# Shematic.net
KiCad netlist of a schematic drawn in Altium Designer
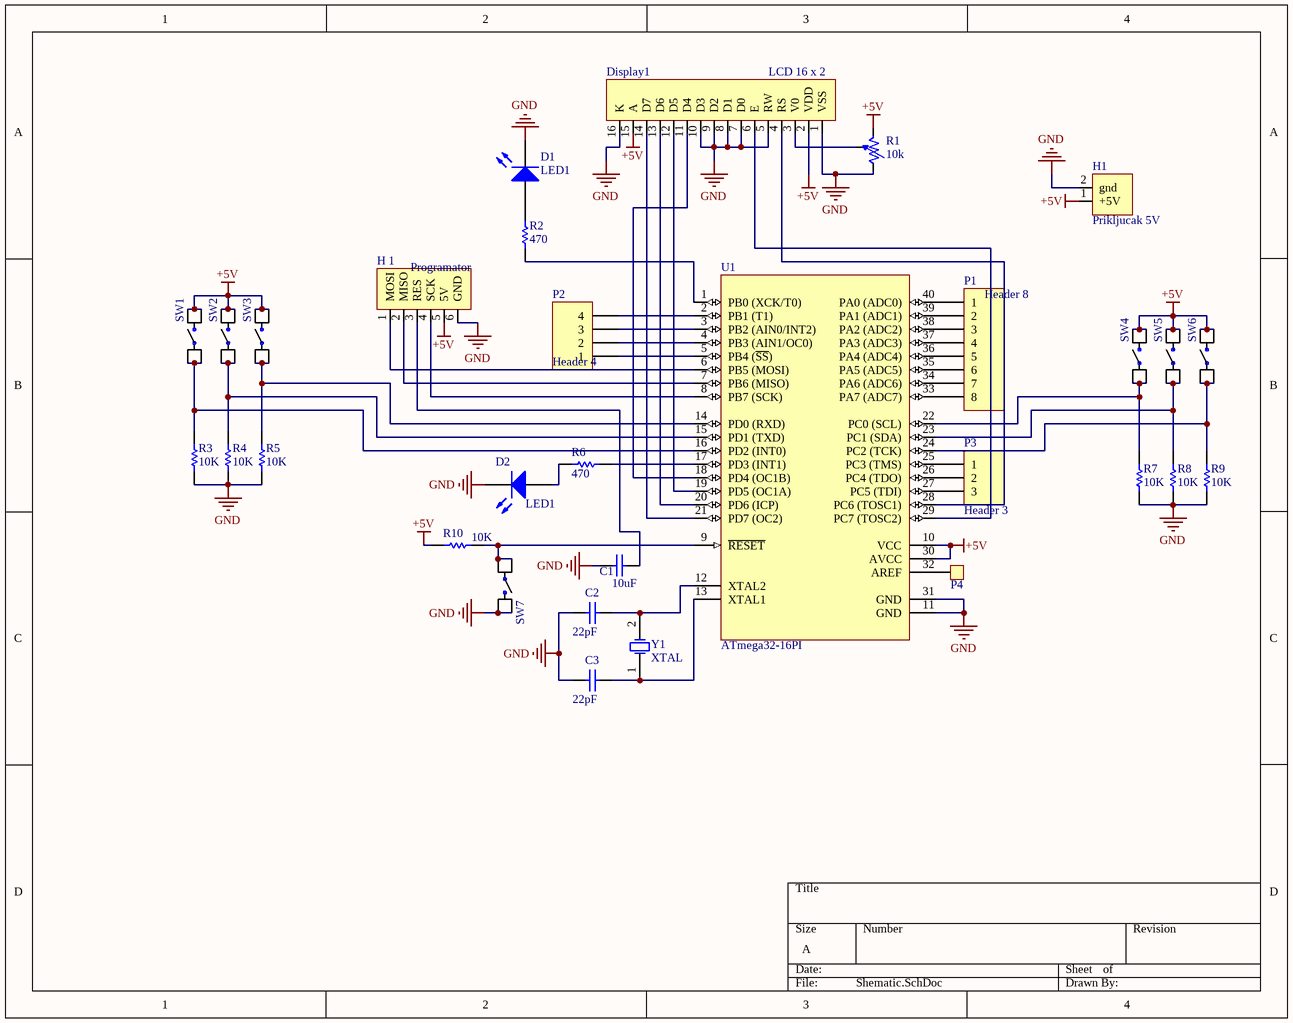
[diagram p0: Shematic.SchDoc]

(export (version "E")
  (design (tool "Eeschema 10.0.6"))
  (components
    (comp (ref "C1")
      (value "10uF")
      (footprint "RAD-0.3")
      (description "Capacitor")
      (fields (field (name "Comment") "Cap") (field (name "PUBLISHER") "Altium Limited"))
      (libsource (lib "Miscellaneous Devices") (part "Cap"))
    )
    (comp (ref "C2")
      (value "22pF")
      (footprint "RAD-0.3")
      (description "Capacitor")
      (fields (field (name "Comment") "Cap") (field (name "PUBLISHER") "Altium Limited"))
      (libsource (lib "Miscellaneous Devices") (part "Cap"))
    )
    (comp (ref "C3")
      (value "22pF")
      (footprint "RAD-0.3")
      (description "Capacitor")
      (fields (field (name "Comment") "Cap") (field (name "PUBLISHER") "Altium Limited"))
      (libsource (lib "Miscellaneous Devices") (part "Cap"))
    )
    (comp (ref "D1")
      (value "LED1")
      (footprint "LED-1")
      (description "Typical RED GaAs LED")
      (fields (field (name "PUBLISHER") "Altium Limited"))
      (libsource (lib "Miscellaneous Devices") (part "LED1"))
    )
    (comp (ref "D2")
      (value "LED1")
      (footprint "LED-1")
      (description "Typical RED GaAs LED")
      (fields (field (name "PUBLISHER") "Altium Limited"))
      (libsource (lib "Miscellaneous Devices") (part "LED1"))
    )
    (comp (ref "Display1")
      (value "LCD 16 x 2")
      (footprint "LCD16x2")
      (libsource (lib "LIB-shematic") (part "LCD 16 X 2"))
    )
    (comp (ref "H 1")
      (value "Programator")
      (footprint "USBASP")
      (libsource (lib "LIB-shematic") (part "USBASP"))
    )
    (comp (ref "H1")
      (value "Prikljucak 5V")
      (footprint "H 5V")
      (libsource (lib "LIB-shematic") (part "Header 5V"))
    )
    (comp (ref "P1")
      (value "Header 8")
      (footprint "HDR1X8")
      (description "Header, 8-Pin")
      (fields (field (name "PUBLISHER") "Altium Limited"))
      (libsource (lib "Miscellaneous Connectors") (part "Header 8"))
    )
    (comp (ref "P2")
      (value "Header 4")
      (footprint "HDR1X4")
      (description "Header, 4-Pin")
      (fields (field (name "PUBLISHER") "Altium Limited"))
      (libsource (lib "Miscellaneous Connectors") (part "Header 4"))
    )
    (comp (ref "P3")
      (value "Header 3")
      (footprint "HDR1X3")
      (description "Header, 3-Pin")
      (fields (field (name "PUBLISHER") "Altium Limited"))
      (libsource (lib "Miscellaneous Connectors") (part "Header 3"))
    )
    (comp (ref "P4")
      (value "Header 1")
      (footprint "Header 1")
      (libsource (lib "LIB-shematic") (part "Header 1"))
    )
    (comp (ref "R1") (value "10k") (footprint "ADJ_RES") (libsource (lib "LIB-shematic") (part "ADJ_RES")))
    (comp (ref "R2")
      (value "470")
      (footprint "AXIAL-0.3")
      (description "Resistor")
      (fields (field (name "Comment") "Res1") (field (name "PUBLISHER") "Altium Limited"))
      (libsource (lib "Miscellaneous Devices") (part "Res1"))
    )
    (comp (ref "R3")
      (value "10K")
      (footprint "AXIAL-0.3")
      (description "Resistor")
      (fields (field (name "Comment") "Res1") (field (name "PUBLISHER") "Altium Limited"))
      (libsource (lib "Miscellaneous Devices") (part "Res1"))
    )
    (comp (ref "R4")
      (value "10K")
      (footprint "AXIAL-0.3")
      (description "Resistor")
      (fields (field (name "Comment") "Res1") (field (name "PUBLISHER") "Altium Limited"))
      (libsource (lib "Miscellaneous Devices") (part "Res1"))
    )
    (comp (ref "R5")
      (value "10K")
      (footprint "AXIAL-0.3")
      (description "Resistor")
      (fields (field (name "Comment") "Res1") (field (name "PUBLISHER") "Altium Limited"))
      (libsource (lib "Miscellaneous Devices") (part "Res1"))
    )
    (comp (ref "R6")
      (value "470")
      (footprint "AXIAL-0.3")
      (description "Resistor")
      (fields (field (name "Comment") "Res1") (field (name "PUBLISHER") "Altium Limited"))
      (libsource (lib "Miscellaneous Devices") (part "Res1"))
    )
    (comp (ref "R7")
      (value "10K")
      (footprint "AXIAL-0.3")
      (description "Resistor")
      (fields (field (name "Comment") "Res1") (field (name "PUBLISHER") "Altium Limited"))
      (libsource (lib "Miscellaneous Devices") (part "Res1"))
    )
    (comp (ref "R8")
      (value "10K")
      (footprint "AXIAL-0.3")
      (description "Resistor")
      (fields (field (name "Comment") "Res1") (field (name "PUBLISHER") "Altium Limited"))
      (libsource (lib "Miscellaneous Devices") (part "Res1"))
    )
    (comp (ref "R9")
      (value "10K")
      (footprint "AXIAL-0.3")
      (description "Resistor")
      (fields (field (name "Comment") "Res1") (field (name "PUBLISHER") "Altium Limited"))
      (libsource (lib "Miscellaneous Devices") (part "Res1"))
    )
    (comp (ref "R10")
      (value "10K")
      (footprint "AXIAL-0.3")
      (description "Resistor")
      (fields (field (name "Comment") "Res1") (field (name "PUBLISHER") "Altium Limited"))
      (libsource (lib "Miscellaneous Devices") (part "Res1"))
    )
    (comp (ref "SW1")
      (value "2-1437565-8")
      (footprint "*SW_SMD_2-1437565-8_4_4.50_6.00_6.00_5.00")
      (description "Tactile Switch SPST-NO Top Actuated Surface Mount")
      (fields (field (name "MF") "TE Connectivity"))
      (libsource (lib "LIB-shematic") (part "2-1437565-8"))
    )
    (comp (ref "SW2")
      (value "2-1437565-8")
      (footprint "*SW_SMD_2-1437565-8_4_4.50_6.00_6.00_5.00")
      (description "Tactile Switch SPST-NO Top Actuated Surface Mount")
      (fields (field (name "MF") "TE Connectivity"))
      (libsource (lib "LIB-shematic") (part "2-1437565-8"))
    )
    (comp (ref "SW3")
      (value "2-1437565-8")
      (footprint "*SW_SMD_2-1437565-8_4_4.50_6.00_6.00_5.00")
      (description "Tactile Switch SPST-NO Top Actuated Surface Mount")
      (fields (field (name "MF") "TE Connectivity"))
      (libsource (lib "LIB-shematic") (part "2-1437565-8"))
    )
    (comp (ref "SW4")
      (value "2-1437565-8")
      (footprint "*SW_SMD_2-1437565-8_4_4.50_6.00_6.00_5.00")
      (description "Tactile Switch SPST-NO Top Actuated Surface Mount")
      (fields (field (name "MF") "TE Connectivity"))
      (libsource (lib "LIB-shematic") (part "2-1437565-8"))
    )
    (comp (ref "SW5")
      (value "2-1437565-8")
      (footprint "*SW_SMD_2-1437565-8_4_4.50_6.00_6.00_5.00")
      (description "Tactile Switch SPST-NO Top Actuated Surface Mount")
      (fields (field (name "MF") "TE Connectivity"))
      (libsource (lib "LIB-shematic") (part "2-1437565-8"))
    )
    (comp (ref "SW6")
      (value "2-1437565-8")
      (footprint "*SW_SMD_2-1437565-8_4_4.50_6.00_6.00_5.00")
      (description "Tactile Switch SPST-NO Top Actuated Surface Mount")
      (fields (field (name "MF") "TE Connectivity"))
      (libsource (lib "LIB-shematic") (part "2-1437565-8"))
    )
    (comp (ref "SW7")
      (value "2-1437565-8")
      (footprint "*SW_SMD_2-1437565-8_4_4.50_6.00_6.00_5.00")
      (description "Tactile Switch SPST-NO Top Actuated Surface Mount")
      (fields (field (name "MF") "TE Connectivity"))
      (libsource (lib "LIB-shematic") (part "2-1437565-8"))
    )
    (comp (ref "U1")
      (value "ATmega32-16PI")
      (footprint "40P6")
      (description "8-Bit AVR Microcontroller with 32K Bytes of In-System Programmable Flash Memory")
      (fields (field (name "PUBLISHER") "Altium Limited"))
      (libsource (lib "Atmel Microcontroller 8-Bit AVR") (part "ATmega32-16PI"))
    )
    (comp (ref "Y1")
      (value "XTAL")
      (footprint "R38")
      (description "Crystal Oscillator")
      (fields (field (name "PUBLISHER") "Altium Limited"))
      (libsource (lib "Miscellaneous Devices") (part "XTAL"))
    )
  )
  (nets
    (net (code "1") (name "+5V") (class "Default")
      (node (ref "Display1") (pin "15") (pinfunction "A_15") (pintype "passive"))
      (node (ref "Display1") (pin "2") (pinfunction "VDD_2") (pintype "passive"))
      (node (ref "H 1") (pin "5") (pinfunction "5V_5") (pintype "passive"))
      (node (ref "H1") (pin "1") (pinfunction "+5V_1") (pintype "passive"))
      (node (ref "R1") (pin "2") (pinfunction "2_2") (pintype "passive"))
      (node (ref "R10") (pin "1") (pinfunction "1_1") (pintype "passive"))
      (node (ref "SW1") (pin "3") (pinfunction "3_3") (pintype "passive"))
      (node (ref "SW1") (pin "4") (pinfunction "4_4") (pintype "passive"))
      (node (ref "SW2") (pin "3") (pinfunction "3_3") (pintype "passive"))
      (node (ref "SW2") (pin "4") (pinfunction "4_4") (pintype "passive"))
      (node (ref "SW3") (pin "3") (pinfunction "3_3") (pintype "passive"))
      (node (ref "SW3") (pin "4") (pinfunction "4_4") (pintype "passive"))
      (node (ref "SW4") (pin "3") (pinfunction "3_3") (pintype "passive"))
      (node (ref "SW4") (pin "4") (pinfunction "4_4") (pintype "passive"))
      (node (ref "SW5") (pin "3") (pinfunction "3_3") (pintype "passive"))
      (node (ref "SW5") (pin "4") (pinfunction "4_4") (pintype "passive"))
      (node (ref "SW6") (pin "3") (pinfunction "3_3") (pintype "passive"))
      (node (ref "SW6") (pin "4") (pinfunction "4_4") (pintype "passive"))
      (node (ref "U1") (pin "10") (pinfunction "VCC_10") (pintype "power_in"))
      (node (ref "U1") (pin "30") (pinfunction "AVCC_30") (pintype "power_in"))
    )
    (net (code "2") (name "GND") (class "Default")
      (node (ref "C1") (pin "2") (pinfunction "2_2") (pintype "passive"))
      (node (ref "C2") (pin "1") (pinfunction "1_1") (pintype "passive"))
      (node (ref "C3") (pin "1") (pinfunction "1_1") (pintype "passive"))
      (node (ref "D1") (pin "2") (pinfunction "K_2") (pintype "passive"))
      (node (ref "D2") (pin "2") (pinfunction "K_2") (pintype "passive"))
      (node (ref "Display1") (pin "1") (pinfunction "VSS_1") (pintype "passive"))
      (node (ref "Display1") (pin "10") (pinfunction "D3_10") (pintype "passive"))
      (node (ref "Display1") (pin "16") (pinfunction "K_16") (pintype "passive"))
      (node (ref "Display1") (pin "5") (pinfunction "RW_5") (pintype "passive"))
      (node (ref "Display1") (pin "7") (pinfunction "D0_7") (pintype "passive"))
      (node (ref "Display1") (pin "8") (pinfunction "D1_8") (pintype "passive"))
      (node (ref "Display1") (pin "9") (pinfunction "D2_9") (pintype "passive"))
      (node (ref "H 1") (pin "6") (pinfunction "GND_6") (pintype "passive"))
      (node (ref "H1") (pin "2") (pinfunction "gnd_2") (pintype "passive"))
      (node (ref "R1") (pin "1") (pinfunction "1_1") (pintype "passive"))
      (node (ref "R3") (pin "1") (pinfunction "1_1") (pintype "passive"))
      (node (ref "R4") (pin "1") (pinfunction "1_1") (pintype "passive"))
      (node (ref "R5") (pin "1") (pinfunction "1_1") (pintype "passive"))
      (node (ref "R7") (pin "1") (pinfunction "1_1") (pintype "passive"))
      (node (ref "R8") (pin "1") (pinfunction "1_1") (pintype "passive"))
      (node (ref "R9") (pin "1") (pinfunction "1_1") (pintype "passive"))
      (node (ref "SW7") (pin "3") (pinfunction "3_3") (pintype "passive"))
      (node (ref "SW7") (pin "4") (pinfunction "4_4") (pintype "passive"))
      (node (ref "U1") (pin "11") (pinfunction "GND_11") (pintype "power_in"))
      (node (ref "U1") (pin "31") (pinfunction "GND_31") (pintype "power_in"))
    )
    (net (code "3") (name "Net-(D1-A)") (class "Default")
      (node (ref "D1") (pin "1") (pinfunction "A_1") (pintype "passive"))
      (node (ref "R2") (pin "1") (pinfunction "1_1") (pintype "passive"))
    )
    (net (code "4") (name "Net-(D2-A)") (class "Default")
      (node (ref "D2") (pin "1") (pinfunction "A_1") (pintype "passive"))
      (node (ref "R6") (pin "2") (pinfunction "2_2") (pintype "passive"))
    )
    (net (code "5") (name "Net-(Display1-D4)") (class "Default")
      (node (ref "Display1") (pin "11") (pinfunction "D4_11") (pintype "passive"))
      (node (ref "U1") (pin "18") (pinfunction "PD4_(OC1B)_18") (pintype "bidirectional"))
    )
    (net (code "6") (name "Net-(Display1-D5)") (class "Default")
      (node (ref "Display1") (pin "12") (pinfunction "D5_12") (pintype "passive"))
      (node (ref "U1") (pin "19") (pinfunction "PD5_(OC1A)_19") (pintype "bidirectional"))
    )
    (net (code "7") (name "Net-(Display1-D6)") (class "Default")
      (node (ref "Display1") (pin "13") (pinfunction "D6_13") (pintype "passive"))
      (node (ref "U1") (pin "20") (pinfunction "PD6_(ICP)_20") (pintype "bidirectional"))
    )
    (net (code "8") (name "Net-(Display1-D7)") (class "Default")
      (node (ref "Display1") (pin "14") (pinfunction "D7_14") (pintype "passive"))
      (node (ref "U1") (pin "21") (pinfunction "PD7_(OC2)_21") (pintype "bidirectional"))
    )
    (net (code "9") (name "Net-(Display1-E)") (class "Default")
      (node (ref "Display1") (pin "6") (pinfunction "E_6") (pintype "passive"))
      (node (ref "U1") (pin "29") (pinfunction "PC7_(TOSC2)_29") (pintype "bidirectional"))
    )
    (net (code "10") (name "Net-(Display1-RS)") (class "Default")
      (node (ref "Display1") (pin "4") (pinfunction "RS_4") (pintype "passive"))
      (node (ref "U1") (pin "28") (pinfunction "PC6_(TOSC1)_28") (pintype "bidirectional"))
    )
    (net (code "11") (name "Net-(Display1-V0)") (class "Default")
      (node (ref "Display1") (pin "3") (pinfunction "V0_3") (pintype "passive"))
      (node (ref "R1") (pin "3") (pinfunction "3_3") (pintype "passive"))
    )
    (net (code "12") (name "Net-(H 1-MISO)") (class "Default")
      (node (ref "H 1") (pin "2") (pinfunction "MISO_2") (pintype "passive"))
      (node (ref "U1") (pin "7") (pinfunction "PB6_(MISO)_7") (pintype "bidirectional"))
    )
    (net (code "13") (name "Net-(H 1-MOSI)") (class "Default")
      (node (ref "H 1") (pin "1") (pinfunction "MOSI_1") (pintype "passive"))
      (node (ref "U1") (pin "6") (pinfunction "PB5_(MOSI)_6") (pintype "bidirectional"))
    )
    (net (code "14") (name "Net-(H 1-RES)") (class "Default")
      (node (ref "C1") (pin "1") (pinfunction "1_1") (pintype "passive"))
      (node (ref "H 1") (pin "3") (pinfunction "RES_3") (pintype "passive"))
    )
    (net (code "15") (name "Net-(H 1-SCK)") (class "Default")
      (node (ref "H 1") (pin "4") (pinfunction "SCK_4") (pintype "passive"))
      (node (ref "U1") (pin "8") (pinfunction "PB7_(SCK)_8") (pintype "bidirectional"))
    )
    (net (code "16") (name "Net-(U1-AREF)") (class "Default")
      (node (ref "P4") (pin "1") (pinfunction "1_1") (pintype "passive"))
      (node (ref "U1") (pin "32") (pinfunction "AREF_32") (pintype "passive"))
    )
    (net (code "17") (name "Net-(U1-PA0_(ADC0))") (class "Default")
      (node (ref "P1") (pin "1") (pinfunction "1_1") (pintype "passive"))
      (node (ref "U1") (pin "40") (pinfunction "PA0_(ADC0)_40") (pintype "bidirectional"))
    )
    (net (code "18") (name "Net-(U1-PA1_(ADC1))") (class "Default")
      (node (ref "P1") (pin "2") (pinfunction "2_2") (pintype "passive"))
      (node (ref "U1") (pin "39") (pinfunction "PA1_(ADC1)_39") (pintype "bidirectional"))
    )
    (net (code "19") (name "Net-(U1-PA2_(ADC2))") (class "Default")
      (node (ref "P1") (pin "3") (pinfunction "3_3") (pintype "passive"))
      (node (ref "U1") (pin "38") (pinfunction "PA2_(ADC2)_38") (pintype "bidirectional"))
    )
    (net (code "20") (name "Net-(U1-PA3_(ADC3))") (class "Default")
      (node (ref "P1") (pin "4") (pinfunction "4_4") (pintype "passive"))
      (node (ref "U1") (pin "37") (pinfunction "PA3_(ADC3)_37") (pintype "bidirectional"))
    )
    (net (code "21") (name "Net-(U1-PA4_(ADC4))") (class "Default")
      (node (ref "P1") (pin "5") (pinfunction "5_5") (pintype "passive"))
      (node (ref "U1") (pin "36") (pinfunction "PA4_(ADC4)_36") (pintype "bidirectional"))
    )
    (net (code "22") (name "Net-(U1-PA5_(ADC5))") (class "Default")
      (node (ref "P1") (pin "6") (pinfunction "6_6") (pintype "passive"))
      (node (ref "U1") (pin "35") (pinfunction "PA5_(ADC5)_35") (pintype "bidirectional"))
    )
    (net (code "23") (name "Net-(U1-PA6_(ADC6))") (class "Default")
      (node (ref "P1") (pin "7") (pinfunction "7_7") (pintype "passive"))
      (node (ref "U1") (pin "34") (pinfunction "PA6_(ADC6)_34") (pintype "bidirectional"))
    )
    (net (code "24") (name "Net-(U1-PA7_(ADC7))") (class "Default")
      (node (ref "P1") (pin "8") (pinfunction "8_8") (pintype "passive"))
      (node (ref "U1") (pin "33") (pinfunction "PA7_(ADC7)_33") (pintype "bidirectional"))
    )
    (net (code "25") (name "Net-(U1-PB0_(XCK{slash}T0))") (class "Default")
      (node (ref "R2") (pin "2") (pinfunction "2_2") (pintype "passive"))
      (node (ref "U1") (pin "1") (pinfunction "PB0_(XCK/T0)_1") (pintype "bidirectional"))
    )
    (net (code "26") (name "Net-(U1-PB1_(T1))") (class "Default")
      (node (ref "P2") (pin "4") (pinfunction "4_4") (pintype "passive"))
      (node (ref "U1") (pin "2") (pinfunction "PB1_(T1)_2") (pintype "bidirectional"))
    )
    (net (code "27") (name "Net-(U1-PB2_(AIN0{slash}INT2))") (class "Default")
      (node (ref "P2") (pin "3") (pinfunction "3_3") (pintype "passive"))
      (node (ref "U1") (pin "3") (pinfunction "PB2_(AIN0/INT2)_3") (pintype "bidirectional"))
    )
    (net (code "28") (name "Net-(U1-PB3_(AIN1{slash}OC0))") (class "Default")
      (node (ref "P2") (pin "2") (pinfunction "2_2") (pintype "passive"))
      (node (ref "U1") (pin "4") (pinfunction "PB3_(AIN1/OC0)_4") (pintype "bidirectional"))
    )
    (net (code "29") (name "Net-(U1-PB4_(~{SS}))") (class "Default")
      (node (ref "P2") (pin "1") (pinfunction "1_1") (pintype "passive"))
      (node (ref "U1") (pin "5") (pinfunction "PB4_(~{SS})_5") (pintype "bidirectional"))
    )
    (net (code "30") (name "Net-(U1-PC0_(SCL))") (class "Default")
      (node (ref "R7") (pin "2") (pinfunction "2_2") (pintype "passive"))
      (node (ref "SW4") (pin "1") (pinfunction "1_1") (pintype "passive"))
      (node (ref "SW4") (pin "2") (pinfunction "2_2") (pintype "passive"))
      (node (ref "U1") (pin "22") (pinfunction "PC0_(SCL)_22") (pintype "bidirectional"))
    )
    (net (code "31") (name "Net-(U1-PC1_(SDA))") (class "Default")
      (node (ref "R8") (pin "2") (pinfunction "2_2") (pintype "passive"))
      (node (ref "SW5") (pin "1") (pinfunction "1_1") (pintype "passive"))
      (node (ref "SW5") (pin "2") (pinfunction "2_2") (pintype "passive"))
      (node (ref "U1") (pin "23") (pinfunction "PC1_(SDA)_23") (pintype "bidirectional"))
    )
    (net (code "32") (name "Net-(U1-PC2_(TCK))") (class "Default")
      (node (ref "R9") (pin "2") (pinfunction "2_2") (pintype "passive"))
      (node (ref "SW6") (pin "1") (pinfunction "1_1") (pintype "passive"))
      (node (ref "SW6") (pin "2") (pinfunction "2_2") (pintype "passive"))
      (node (ref "U1") (pin "24") (pinfunction "PC2_(TCK)_24") (pintype "bidirectional"))
    )
    (net (code "33") (name "Net-(U1-PC3_(TMS))") (class "Default")
      (node (ref "P3") (pin "1") (pinfunction "1_1") (pintype "passive"))
      (node (ref "U1") (pin "25") (pinfunction "PC3_(TMS)_25") (pintype "bidirectional"))
    )
    (net (code "34") (name "Net-(U1-PC4_(TDO))") (class "Default")
      (node (ref "P3") (pin "2") (pinfunction "2_2") (pintype "passive"))
      (node (ref "U1") (pin "26") (pinfunction "PC4_(TDO)_26") (pintype "bidirectional"))
    )
    (net (code "35") (name "Net-(U1-PC5_(TDI))") (class "Default")
      (node (ref "P3") (pin "3") (pinfunction "3_3") (pintype "passive"))
      (node (ref "U1") (pin "27") (pinfunction "PC5_(TDI)_27") (pintype "bidirectional"))
    )
    (net (code "36") (name "Net-(U1-PD0_(RXD))") (class "Default")
      (node (ref "R5") (pin "2") (pinfunction "2_2") (pintype "passive"))
      (node (ref "SW3") (pin "1") (pinfunction "1_1") (pintype "passive"))
      (node (ref "SW3") (pin "2") (pinfunction "2_2") (pintype "passive"))
      (node (ref "U1") (pin "14") (pinfunction "PD0_(RXD)_14") (pintype "bidirectional"))
    )
    (net (code "37") (name "Net-(U1-PD1_(TXD))") (class "Default")
      (node (ref "R4") (pin "2") (pinfunction "2_2") (pintype "passive"))
      (node (ref "SW2") (pin "1") (pinfunction "1_1") (pintype "passive"))
      (node (ref "SW2") (pin "2") (pinfunction "2_2") (pintype "passive"))
      (node (ref "U1") (pin "15") (pinfunction "PD1_(TXD)_15") (pintype "bidirectional"))
    )
    (net (code "38") (name "Net-(U1-PD2_(INT0))") (class "Default")
      (node (ref "R3") (pin "2") (pinfunction "2_2") (pintype "passive"))
      (node (ref "SW1") (pin "1") (pinfunction "1_1") (pintype "passive"))
      (node (ref "SW1") (pin "2") (pinfunction "2_2") (pintype "passive"))
      (node (ref "U1") (pin "16") (pinfunction "PD2_(INT0)_16") (pintype "bidirectional"))
    )
    (net (code "39") (name "Net-(U1-PD3_(INT1))") (class "Default")
      (node (ref "R6") (pin "1") (pinfunction "1_1") (pintype "passive"))
      (node (ref "U1") (pin "17") (pinfunction "PD3_(INT1)_17") (pintype "bidirectional"))
    )
    (net (code "40") (name "Net-(U1-XTAL1)") (class "Default")
      (node (ref "C3") (pin "2") (pinfunction "2_2") (pintype "passive"))
      (node (ref "U1") (pin "13") (pinfunction "XTAL1_13") (pintype "passive"))
      (node (ref "Y1") (pin "1") (pinfunction "OSC1_1") (pintype "passive"))
    )
    (net (code "41") (name "Net-(U1-XTAL2)") (class "Default")
      (node (ref "C2") (pin "2") (pinfunction "2_2") (pintype "passive"))
      (node (ref "U1") (pin "12") (pinfunction "XTAL2_12") (pintype "passive"))
      (node (ref "Y1") (pin "2") (pinfunction "OSC2_2") (pintype "passive"))
    )
    (net (code "42") (name "Net-(U1-~{RESET})") (class "Default")
      (node (ref "R10") (pin "2") (pinfunction "2_2") (pintype "passive"))
      (node (ref "SW7") (pin "1") (pinfunction "1_1") (pintype "passive"))
      (node (ref "SW7") (pin "2") (pinfunction "2_2") (pintype "passive"))
      (node (ref "U1") (pin "9") (pinfunction "~{RESET}_9") (pintype "input"))
    )
  )
)
